# DigitalLabBoard_Switches.net
KiCad netlist of a schematic drawn in Altium Designer
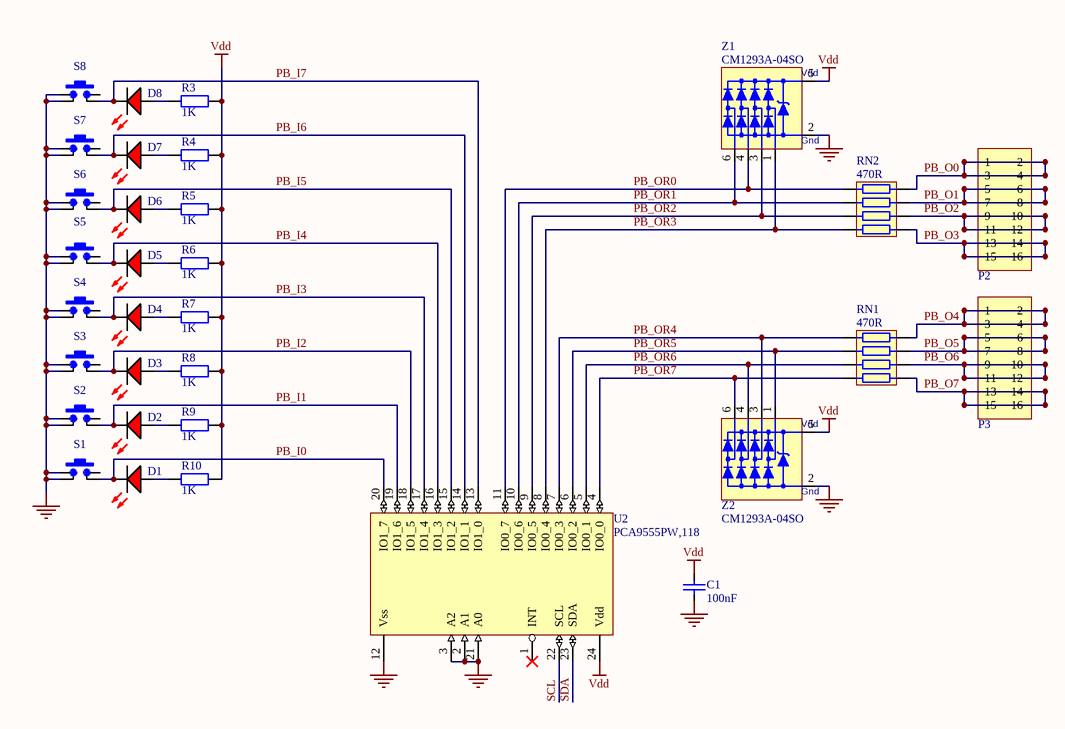
[diagram p0: DigitalLabBoard_Switches.SchDoc]

(export (version "E")
  (design (tool "Eeschema 10.0.6"))
  (components
    (comp (ref "C1")
      (value "100nF")
      (footprint "CCNP1608-0603")
      (description "Capacitor non-polar SMT 0603")
      (fields
        (field (name "MANUFACTURER") "Generic Components")
        (field (name "PUBLISHER") "Altium Hobart Technology Centre")
      )
      (libsource (lib "MyLibrary") (part "Cap_CCNP_0603"))
    )
    (comp (ref "D1")
      (value "LED Red")
      (footprint "LED1608-0603-RED")
      (description "LED 0603 Red")
      (fields (field (name "MANUFACTURER") "Generic Components") (field (name "PUBLISHER") "Altium Limited"))
      (libsource (lib "MySchLib") (part "LED-0603-Red"))
    )
    (comp (ref "D2")
      (value "LED Red")
      (footprint "LED1608-0603-RED")
      (description "LED 0603 Red")
      (fields (field (name "MANUFACTURER") "Generic Components") (field (name "PUBLISHER") "Altium Limited"))
      (libsource (lib "MySchLib") (part "LED-0603-Red"))
    )
    (comp (ref "D3")
      (value "LED Red")
      (footprint "LED1608-0603-RED")
      (description "LED 0603 Red")
      (fields (field (name "MANUFACTURER") "Generic Components") (field (name "PUBLISHER") "Altium Limited"))
      (libsource (lib "MySchLib") (part "LED-0603-Red"))
    )
    (comp (ref "D4")
      (value "LED Red")
      (footprint "LED1608-0603-RED")
      (description "LED 0603 Red")
      (fields (field (name "MANUFACTURER") "Generic Components") (field (name "PUBLISHER") "Altium Limited"))
      (libsource (lib "MySchLib") (part "LED-0603-Red"))
    )
    (comp (ref "D5")
      (value "LED Red")
      (footprint "LED1608-0603-RED")
      (description "LED 0603 Red")
      (fields (field (name "MANUFACTURER") "Generic Components") (field (name "PUBLISHER") "Altium Limited"))
      (libsource (lib "MySchLib") (part "LED-0603-Red"))
    )
    (comp (ref "D6")
      (value "LED Red")
      (footprint "LED1608-0603-RED")
      (description "LED 0603 Red")
      (fields (field (name "MANUFACTURER") "Generic Components") (field (name "PUBLISHER") "Altium Limited"))
      (libsource (lib "MySchLib") (part "LED-0603-Red"))
    )
    (comp (ref "D7")
      (value "LED Red")
      (footprint "LED1608-0603-RED")
      (description "LED 0603 Red")
      (fields (field (name "MANUFACTURER") "Generic Components") (field (name "PUBLISHER") "Altium Limited"))
      (libsource (lib "MySchLib") (part "LED-0603-Red"))
    )
    (comp (ref "D8")
      (value "LED Red")
      (footprint "LED1608-0603-RED")
      (description "LED 0603 Red")
      (fields (field (name "MANUFACTURER") "Generic Components") (field (name "PUBLISHER") "Altium Limited"))
      (libsource (lib "MySchLib") (part "LED-0603-Red"))
    )
    (comp (ref "P2")
      (value "Header 2x8")
      (footprint "HDR2X8S")
      (libsource (lib "MyLibrary") (part "Header 2x8"))
    )
    (comp (ref "P3")
      (value "Header 2x8")
      (footprint "HDR2X8S")
      (libsource (lib "MyLibrary") (part "Header 2x8"))
    )
    (comp (ref "R3")
      (value "1K")
      (footprint "CR1608-0603")
      (description "Resistor SMT 0603")
      (fields
        (field (name "MANUFACTURER") "Generic Components")
        (field (name "PUBLISHER") "Altium Hobart Technology Centre")
      )
      (libsource (lib "MyLibrary") (part "Res_CR0603"))
    )
    (comp (ref "R4")
      (value "1K")
      (footprint "CR1608-0603")
      (description "Resistor SMT 0603")
      (fields
        (field (name "MANUFACTURER") "Generic Components")
        (field (name "PUBLISHER") "Altium Hobart Technology Centre")
      )
      (libsource (lib "MyLibrary") (part "Res_CR0603"))
    )
    (comp (ref "R5")
      (value "1K")
      (footprint "CR1608-0603")
      (description "Resistor SMT 0603")
      (fields
        (field (name "MANUFACTURER") "Generic Components")
        (field (name "PUBLISHER") "Altium Hobart Technology Centre")
      )
      (libsource (lib "MyLibrary") (part "Res_CR0603"))
    )
    (comp (ref "R6")
      (value "1K")
      (footprint "CR1608-0603")
      (description "Resistor SMT 0603")
      (fields
        (field (name "MANUFACTURER") "Generic Components")
        (field (name "PUBLISHER") "Altium Hobart Technology Centre")
      )
      (libsource (lib "MyLibrary") (part "Res_CR0603"))
    )
    (comp (ref "R7")
      (value "1K")
      (footprint "CR1608-0603")
      (description "Resistor SMT 0603")
      (fields
        (field (name "MANUFACTURER") "Generic Components")
        (field (name "PUBLISHER") "Altium Hobart Technology Centre")
      )
      (libsource (lib "MyLibrary") (part "Res_CR0603"))
    )
    (comp (ref "R8")
      (value "1K")
      (footprint "CR1608-0603")
      (description "Resistor SMT 0603")
      (fields
        (field (name "MANUFACTURER") "Generic Components")
        (field (name "PUBLISHER") "Altium Hobart Technology Centre")
      )
      (libsource (lib "MyLibrary") (part "Res_CR0603"))
    )
    (comp (ref "R9")
      (value "1K")
      (footprint "CR1608-0603")
      (description "Resistor SMT 0603")
      (fields
        (field (name "MANUFACTURER") "Generic Components")
        (field (name "PUBLISHER") "Altium Hobart Technology Centre")
      )
      (libsource (lib "MyLibrary") (part "Res_CR0603"))
    )
    (comp (ref "R10")
      (value "1K")
      (footprint "CR1608-0603")
      (description "Resistor SMT 0603")
      (fields
        (field (name "MANUFACTURER") "Generic Components")
        (field (name "PUBLISHER") "Altium Hobart Technology Centre")
      )
      (libsource (lib "MyLibrary") (part "Res_CR0603"))
    )
    (comp (ref "RN1")
      (value "470R")
      (footprint "CR1206-0603_X4_N")
      (description "SMT x4 Resistor Array")
      (libsource (lib "MyLibrary") (part "ResistorNetwork_CR0603x4"))
    )
    (comp (ref "RN2")
      (value "470R")
      (footprint "CR1206-0603_X4_N")
      (description "SMT x4 Resistor Array")
      (libsource (lib "MyLibrary") (part "ResistorNetwork_CR0603x4"))
    )
    (comp (ref "S1")
      (value "~")
      (footprint "SMD-SW-4_5.1x5.1x2.0_M")
      (description "Tactile Switch SPST 5.10mm X 5.10mm\r\n(1.5mm=C318884)\r\n(2.0mm=C318888)\r\n(3.5mm=C318886)")
      (libsource (lib "MySchLib") (part "SW_PB-TS"))
    )
    (comp (ref "S2")
      (value "~")
      (footprint "SMD-SW-4_5.1x5.1x2.0_M")
      (description "Tactile Switch SPST 5.10mm X 5.10mm\r\n(1.5mm=C318884)\r\n(2.0mm=C318888)\r\n(3.5mm=C318886)")
      (libsource (lib "MySchLib") (part "SW_PB-TS"))
    )
    (comp (ref "S3")
      (value "~")
      (footprint "SMD-SW-4_5.1x5.1x2.0_M")
      (description "Tactile Switch SPST 5.10mm X 5.10mm\r\n(1.5mm=C318884)\r\n(2.0mm=C318888)\r\n(3.5mm=C318886)")
      (libsource (lib "MySchLib") (part "SW_PB-TS"))
    )
    (comp (ref "S4")
      (value "~")
      (footprint "SMD-SW-4_5.1x5.1x2.0_M")
      (description "Tactile Switch SPST 5.10mm X 5.10mm\r\n(1.5mm=C318884)\r\n(2.0mm=C318888)\r\n(3.5mm=C318886)")
      (libsource (lib "MySchLib") (part "SW_PB-TS"))
    )
    (comp (ref "S5")
      (value "~")
      (footprint "SMD-SW-4_5.1x5.1x2.0_M")
      (description "Tactile Switch SPST 5.10mm X 5.10mm\r\n(1.5mm=C318884)\r\n(2.0mm=C318888)\r\n(3.5mm=C318886)")
      (libsource (lib "MySchLib") (part "SW_PB-TS"))
    )
    (comp (ref "S6")
      (value "~")
      (footprint "SMD-SW-4_5.1x5.1x2.0_M")
      (description "Tactile Switch SPST 5.10mm X 5.10mm\r\n(1.5mm=C318884)\r\n(2.0mm=C318888)\r\n(3.5mm=C318886)")
      (libsource (lib "MySchLib") (part "SW_PB-TS"))
    )
    (comp (ref "S7")
      (value "~")
      (footprint "SMD-SW-4_5.1x5.1x2.0_M")
      (description "Tactile Switch SPST 5.10mm X 5.10mm\r\n(1.5mm=C318884)\r\n(2.0mm=C318888)\r\n(3.5mm=C318886)")
      (libsource (lib "MySchLib") (part "SW_PB-TS"))
    )
    (comp (ref "S8")
      (value "~")
      (footprint "SMD-SW-4_5.1x5.1x2.0_M")
      (description "Tactile Switch SPST 5.10mm X 5.10mm\r\n(1.5mm=C318884)\r\n(2.0mm=C318888)\r\n(3.5mm=C318886)")
      (libsource (lib "MySchLib") (part "SW_PB-TS"))
    )
    (comp (ref "U2")
      (value "PCA9555PW,118")
      (footprint "TSSOP24_N")
      (description "16-bit I2C I/O Expander (TSSOP24)\r\nPUPs on I/O pins")
      (libsource (lib "MySchLib") (part "PCA9555PW,118"))
    )
    (comp (ref "Z1")
      (value "CM1293A-04SO")
      (footprint "SOT457_N")
      (description "Ultra low capacitance quadruple rail-to-rail ESD protection")
      (libsource (lib "") (part "CM1293A-04SO_1"))
    )
    (comp (ref "Z2")
      (value "CM1293A-04SO")
      (footprint "SOT457_N")
      (description "Ultra low capacitance quadruple rail-to-rail ESD protection")
      (libsource (lib "MySchLib") (part "CM1293A-04SO"))
    )
  )
  (nets
    (net (code "1") (name "/PB_I0") (class "Default")
      (node (ref "D1") (pin "K") (pinfunction "K_K") (pintype "passive"))
      (node (ref "S1") (pin "2") (pinfunction "2_2") (pintype "passive"))
      (node (ref "U2") (pin "20") (pinfunction "IO1_7_20") (pintype "bidirectional"))
    )
    (net (code "2") (name "/PB_I1") (class "Default")
      (node (ref "D2") (pin "K") (pinfunction "K_K") (pintype "passive"))
      (node (ref "S2") (pin "2") (pinfunction "2_2") (pintype "passive"))
      (node (ref "U2") (pin "19") (pinfunction "IO1_6_19") (pintype "bidirectional"))
    )
    (net (code "3") (name "/PB_I2") (class "Default")
      (node (ref "D3") (pin "K") (pinfunction "K_K") (pintype "passive"))
      (node (ref "S3") (pin "2") (pinfunction "2_2") (pintype "passive"))
      (node (ref "U2") (pin "18") (pinfunction "IO1_5_18") (pintype "bidirectional"))
    )
    (net (code "4") (name "/PB_I3") (class "Default")
      (node (ref "D4") (pin "K") (pinfunction "K_K") (pintype "passive"))
      (node (ref "S4") (pin "2") (pinfunction "2_2") (pintype "passive"))
      (node (ref "U2") (pin "17") (pinfunction "IO1_4_17") (pintype "bidirectional"))
    )
    (net (code "5") (name "/PB_I4") (class "Default")
      (node (ref "D5") (pin "K") (pinfunction "K_K") (pintype "passive"))
      (node (ref "S5") (pin "2") (pinfunction "2_2") (pintype "passive"))
      (node (ref "U2") (pin "16") (pinfunction "IO1_3_16") (pintype "bidirectional"))
    )
    (net (code "6") (name "/PB_I5") (class "Default")
      (node (ref "D6") (pin "K") (pinfunction "K_K") (pintype "passive"))
      (node (ref "S6") (pin "2") (pinfunction "2_2") (pintype "passive"))
      (node (ref "U2") (pin "15") (pinfunction "IO1_2_15") (pintype "bidirectional"))
    )
    (net (code "7") (name "/PB_I6") (class "Default")
      (node (ref "D7") (pin "K") (pinfunction "K_K") (pintype "passive"))
      (node (ref "S7") (pin "2") (pinfunction "2_2") (pintype "passive"))
      (node (ref "U2") (pin "14") (pinfunction "IO1_1_14") (pintype "bidirectional"))
    )
    (net (code "8") (name "/PB_I7") (class "Default")
      (node (ref "D8") (pin "K") (pinfunction "K_K") (pintype "passive"))
      (node (ref "S8") (pin "2") (pinfunction "2_2") (pintype "passive"))
      (node (ref "U2") (pin "13") (pinfunction "IO1_0_13") (pintype "bidirectional"))
    )
    (net (code "9") (name "/PB_O0") (class "Default")
      (node (ref "P2") (pin "1") (pinfunction "1_1") (pintype "passive"))
      (node (ref "P2") (pin "2") (pinfunction "2_2") (pintype "passive"))
      (node (ref "P2") (pin "3") (pinfunction "3_3") (pintype "passive"))
      (node (ref "P2") (pin "4") (pinfunction "4_4") (pintype "passive"))
      (node (ref "RN2") (pin "4") (pinfunction "4_4") (pintype "passive"))
    )
    (net (code "10") (name "/PB_O1") (class "Default")
      (node (ref "P2") (pin "5") (pinfunction "5_5") (pintype "passive"))
      (node (ref "P2") (pin "6") (pinfunction "6_6") (pintype "passive"))
      (node (ref "P2") (pin "7") (pinfunction "7_7") (pintype "passive"))
      (node (ref "P2") (pin "8") (pinfunction "8_8") (pintype "passive"))
      (node (ref "RN2") (pin "3") (pinfunction "3_3") (pintype "passive"))
    )
    (net (code "11") (name "/PB_O2") (class "Default")
      (node (ref "P2") (pin "10") (pinfunction "10_10") (pintype "passive"))
      (node (ref "P2") (pin "11") (pinfunction "11_11") (pintype "passive"))
      (node (ref "P2") (pin "12") (pinfunction "12_12") (pintype "passive"))
      (node (ref "P2") (pin "9") (pinfunction "9_9") (pintype "passive"))
      (node (ref "RN2") (pin "2") (pinfunction "2_2") (pintype "passive"))
    )
    (net (code "12") (name "/PB_O3") (class "Default")
      (node (ref "P2") (pin "13") (pinfunction "13_13") (pintype "passive"))
      (node (ref "P2") (pin "14") (pinfunction "14_14") (pintype "passive"))
      (node (ref "P2") (pin "15") (pinfunction "15_15") (pintype "passive"))
      (node (ref "P2") (pin "16") (pinfunction "16_16") (pintype "passive"))
      (node (ref "RN2") (pin "1") (pinfunction "1_1") (pintype "passive"))
    )
    (net (code "13") (name "/PB_O4") (class "Default")
      (node (ref "P3") (pin "1") (pinfunction "1_1") (pintype "passive"))
      (node (ref "P3") (pin "2") (pinfunction "2_2") (pintype "passive"))
      (node (ref "P3") (pin "3") (pinfunction "3_3") (pintype "passive"))
      (node (ref "P3") (pin "4") (pinfunction "4_4") (pintype "passive"))
      (node (ref "RN1") (pin "4") (pinfunction "4_4") (pintype "passive"))
    )
    (net (code "14") (name "/PB_O5") (class "Default")
      (node (ref "P3") (pin "5") (pinfunction "5_5") (pintype "passive"))
      (node (ref "P3") (pin "6") (pinfunction "6_6") (pintype "passive"))
      (node (ref "P3") (pin "7") (pinfunction "7_7") (pintype "passive"))
      (node (ref "P3") (pin "8") (pinfunction "8_8") (pintype "passive"))
      (node (ref "RN1") (pin "3") (pinfunction "3_3") (pintype "passive"))
    )
    (net (code "15") (name "/PB_O6") (class "Default")
      (node (ref "P3") (pin "10") (pinfunction "10_10") (pintype "passive"))
      (node (ref "P3") (pin "11") (pinfunction "11_11") (pintype "passive"))
      (node (ref "P3") (pin "12") (pinfunction "12_12") (pintype "passive"))
      (node (ref "P3") (pin "9") (pinfunction "9_9") (pintype "passive"))
      (node (ref "RN1") (pin "2") (pinfunction "2_2") (pintype "passive"))
    )
    (net (code "16") (name "/PB_O7") (class "Default")
      (node (ref "P3") (pin "13") (pinfunction "13_13") (pintype "passive"))
      (node (ref "P3") (pin "14") (pinfunction "14_14") (pintype "passive"))
      (node (ref "P3") (pin "15") (pinfunction "15_15") (pintype "passive"))
      (node (ref "P3") (pin "16") (pinfunction "16_16") (pintype "passive"))
      (node (ref "RN1") (pin "1") (pinfunction "1_1") (pintype "passive"))
    )
    (net (code "17") (name "/PB_OR0") (class "Default")
      (node (ref "RN2") (pin "5") (pinfunction "5_5") (pintype "passive"))
      (node (ref "U2") (pin "11") (pinfunction "IO0_7_11") (pintype "bidirectional"))
      (node (ref "Z1") (pin "4") (pintype "passive"))
    )
    (net (code "18") (name "/PB_OR1") (class "Default")
      (node (ref "RN2") (pin "6") (pinfunction "6_6") (pintype "passive"))
      (node (ref "U2") (pin "10") (pinfunction "IO0_6_10") (pintype "bidirectional"))
      (node (ref "Z1") (pin "6") (pintype "passive"))
    )
    (net (code "19") (name "/PB_OR2") (class "Default")
      (node (ref "RN2") (pin "7") (pinfunction "7_7") (pintype "passive"))
      (node (ref "U2") (pin "9") (pinfunction "IO0_5_9") (pintype "bidirectional"))
      (node (ref "Z1") (pin "3") (pintype "passive"))
    )
    (net (code "20") (name "/PB_OR3") (class "Default")
      (node (ref "RN2") (pin "8") (pinfunction "8_8") (pintype "passive"))
      (node (ref "U2") (pin "8") (pinfunction "IO0_4_8") (pintype "bidirectional"))
      (node (ref "Z1") (pin "1") (pintype "passive"))
    )
    (net (code "21") (name "/PB_OR4") (class "Default")
      (node (ref "RN1") (pin "5") (pinfunction "5_5") (pintype "passive"))
      (node (ref "U2") (pin "7") (pinfunction "IO0_3_7") (pintype "bidirectional"))
      (node (ref "Z2") (pin "3") (pintype "passive"))
    )
    (net (code "22") (name "/PB_OR5") (class "Default")
      (node (ref "RN1") (pin "6") (pinfunction "6_6") (pintype "passive"))
      (node (ref "U2") (pin "6") (pinfunction "IO0_2_6") (pintype "bidirectional"))
      (node (ref "Z2") (pin "1") (pintype "passive"))
    )
    (net (code "23") (name "/PB_OR6") (class "Default")
      (node (ref "RN1") (pin "7") (pinfunction "7_7") (pintype "passive"))
      (node (ref "U2") (pin "5") (pinfunction "IO0_1_5") (pintype "bidirectional"))
      (node (ref "Z2") (pin "4") (pintype "passive"))
    )
    (net (code "24") (name "/PB_OR7") (class "Default")
      (node (ref "RN1") (pin "8") (pinfunction "8_8") (pintype "passive"))
      (node (ref "U2") (pin "4") (pinfunction "IO0_0_4") (pintype "bidirectional"))
      (node (ref "Z2") (pin "6") (pintype "passive"))
    )
    (net (code "25") (name "/SCL") (class "Default")
      (node (ref "U2") (pin "22") (pinfunction "SCL_22") (pintype "bidirectional"))
    )
    (net (code "26") (name "/SDA") (class "Default")
      (node (ref "U2") (pin "23") (pinfunction "SDA_23") (pintype "bidirectional"))
    )
    (net (code "27") (name "GND") (class "Default")
      (node (ref "C1") (pin "1") (pinfunction "1_1") (pintype "passive"))
      (node (ref "S1") (pin "1") (pinfunction "1_1") (pintype "passive"))
      (node (ref "S1") (pin "1b") (pinfunction "1b_1b") (pintype "passive"))
      (node (ref "S2") (pin "1") (pinfunction "1_1") (pintype "passive"))
      (node (ref "S2") (pin "1b") (pinfunction "1b_1b") (pintype "passive"))
      (node (ref "S3") (pin "1") (pinfunction "1_1") (pintype "passive"))
      (node (ref "S3") (pin "1b") (pinfunction "1b_1b") (pintype "passive"))
      (node (ref "S4") (pin "1") (pinfunction "1_1") (pintype "passive"))
      (node (ref "S4") (pin "1b") (pinfunction "1b_1b") (pintype "passive"))
      (node (ref "S5") (pin "1") (pinfunction "1_1") (pintype "passive"))
      (node (ref "S5") (pin "1b") (pinfunction "1b_1b") (pintype "passive"))
      (node (ref "S6") (pin "1") (pinfunction "1_1") (pintype "passive"))
      (node (ref "S6") (pin "1b") (pinfunction "1b_1b") (pintype "passive"))
      (node (ref "S7") (pin "1") (pinfunction "1_1") (pintype "passive"))
      (node (ref "S7") (pin "1b") (pinfunction "1b_1b") (pintype "passive"))
      (node (ref "S8") (pin "1") (pinfunction "1_1") (pintype "passive"))
      (node (ref "S8") (pin "1b") (pinfunction "1b_1b") (pintype "passive"))
      (node (ref "U2") (pin "12") (pinfunction "Vss_12") (pintype "power_in"))
      (node (ref "U2") (pin "2") (pinfunction "A1_2") (pintype "input"))
      (node (ref "U2") (pin "21") (pinfunction "A0_21") (pintype "input"))
      (node (ref "U2") (pin "3") (pinfunction "A2_3") (pintype "input"))
      (node (ref "Z1") (pin "2") (pinfunction "Vn_2") (pintype "passive"))
      (node (ref "Z2") (pin "2") (pinfunction "Vn_2") (pintype "passive"))
    )
    (net (code "28") (name "Net-(D1-PadA)") (class "Default")
      (node (ref "D1") (pin "A") (pinfunction "A_A") (pintype "passive"))
      (node (ref "R10") (pin "1") (pinfunction "1_1") (pintype "passive"))
    )
    (net (code "29") (name "Net-(D2-PadA)") (class "Default")
      (node (ref "D2") (pin "A") (pinfunction "A_A") (pintype "passive"))
      (node (ref "R9") (pin "1") (pinfunction "1_1") (pintype "passive"))
    )
    (net (code "30") (name "Net-(D3-PadA)") (class "Default")
      (node (ref "D3") (pin "A") (pinfunction "A_A") (pintype "passive"))
      (node (ref "R8") (pin "1") (pinfunction "1_1") (pintype "passive"))
    )
    (net (code "31") (name "Net-(D4-PadA)") (class "Default")
      (node (ref "D4") (pin "A") (pinfunction "A_A") (pintype "passive"))
      (node (ref "R7") (pin "1") (pinfunction "1_1") (pintype "passive"))
    )
    (net (code "32") (name "Net-(D5-PadA)") (class "Default")
      (node (ref "D5") (pin "A") (pinfunction "A_A") (pintype "passive"))
      (node (ref "R6") (pin "1") (pinfunction "1_1") (pintype "passive"))
    )
    (net (code "33") (name "Net-(D6-PadA)") (class "Default")
      (node (ref "D6") (pin "A") (pinfunction "A_A") (pintype "passive"))
      (node (ref "R5") (pin "1") (pinfunction "1_1") (pintype "passive"))
    )
    (net (code "34") (name "Net-(D7-PadA)") (class "Default")
      (node (ref "D7") (pin "A") (pinfunction "A_A") (pintype "passive"))
      (node (ref "R4") (pin "1") (pinfunction "1_1") (pintype "passive"))
    )
    (net (code "35") (name "Net-(D8-PadA)") (class "Default")
      (node (ref "D8") (pin "A") (pinfunction "A_A") (pintype "passive"))
      (node (ref "R3") (pin "1") (pinfunction "1_1") (pintype "passive"))
    )
    (net (code "36") (name "Vdd") (class "Default")
      (node (ref "C1") (pin "2") (pinfunction "2_2") (pintype "passive"))
      (node (ref "R10") (pin "2") (pinfunction "2_2") (pintype "passive"))
      (node (ref "R3") (pin "2") (pinfunction "2_2") (pintype "passive"))
      (node (ref "R4") (pin "2") (pinfunction "2_2") (pintype "passive"))
      (node (ref "R5") (pin "2") (pinfunction "2_2") (pintype "passive"))
      (node (ref "R6") (pin "2") (pinfunction "2_2") (pintype "passive"))
      (node (ref "R7") (pin "2") (pinfunction "2_2") (pintype "passive"))
      (node (ref "R8") (pin "2") (pinfunction "2_2") (pintype "passive"))
      (node (ref "R9") (pin "2") (pinfunction "2_2") (pintype "passive"))
      (node (ref "U2") (pin "24") (pinfunction "Vdd_24") (pintype "power_in"))
      (node (ref "Z1") (pin "5") (pinfunction "Vp_5") (pintype "passive"))
      (node (ref "Z2") (pin "5") (pinfunction "Vp_5") (pintype "passive"))
    )
    (net (code "37") (name "unconnected-(S1-Pad2b)") (class "Default")
      (node (ref "S1") (pin "2b") (pinfunction "2b_2b") (pintype "passive"))
    )
    (net (code "38") (name "unconnected-(S2-Pad2b)") (class "Default")
      (node (ref "S2") (pin "2b") (pinfunction "2b_2b") (pintype "passive"))
    )
    (net (code "39") (name "unconnected-(S3-Pad2b)") (class "Default")
      (node (ref "S3") (pin "2b") (pinfunction "2b_2b") (pintype "passive"))
    )
    (net (code "40") (name "unconnected-(S4-Pad2b)") (class "Default")
      (node (ref "S4") (pin "2b") (pinfunction "2b_2b") (pintype "passive"))
    )
    (net (code "41") (name "unconnected-(S5-Pad2b)") (class "Default")
      (node (ref "S5") (pin "2b") (pinfunction "2b_2b") (pintype "passive"))
    )
    (net (code "42") (name "unconnected-(S6-Pad2b)") (class "Default")
      (node (ref "S6") (pin "2b") (pinfunction "2b_2b") (pintype "passive"))
    )
    (net (code "43") (name "unconnected-(S7-Pad2b)") (class "Default")
      (node (ref "S7") (pin "2b") (pinfunction "2b_2b") (pintype "passive"))
    )
    (net (code "44") (name "unconnected-(S8-Pad2b)") (class "Default")
      (node (ref "S8") (pin "2b") (pinfunction "2b_2b") (pintype "passive"))
    )
    (net (code "45") (name "unconnected-(U2-INT-Pad1)") (class "Default")
      (node (ref "U2") (pin "1") (pinfunction "INT_1") (pintype "open_collector+no_connect"))
    )
  )
)
